# port-expander.net
KiCad netlist of a schematic drawn in Altium Designer
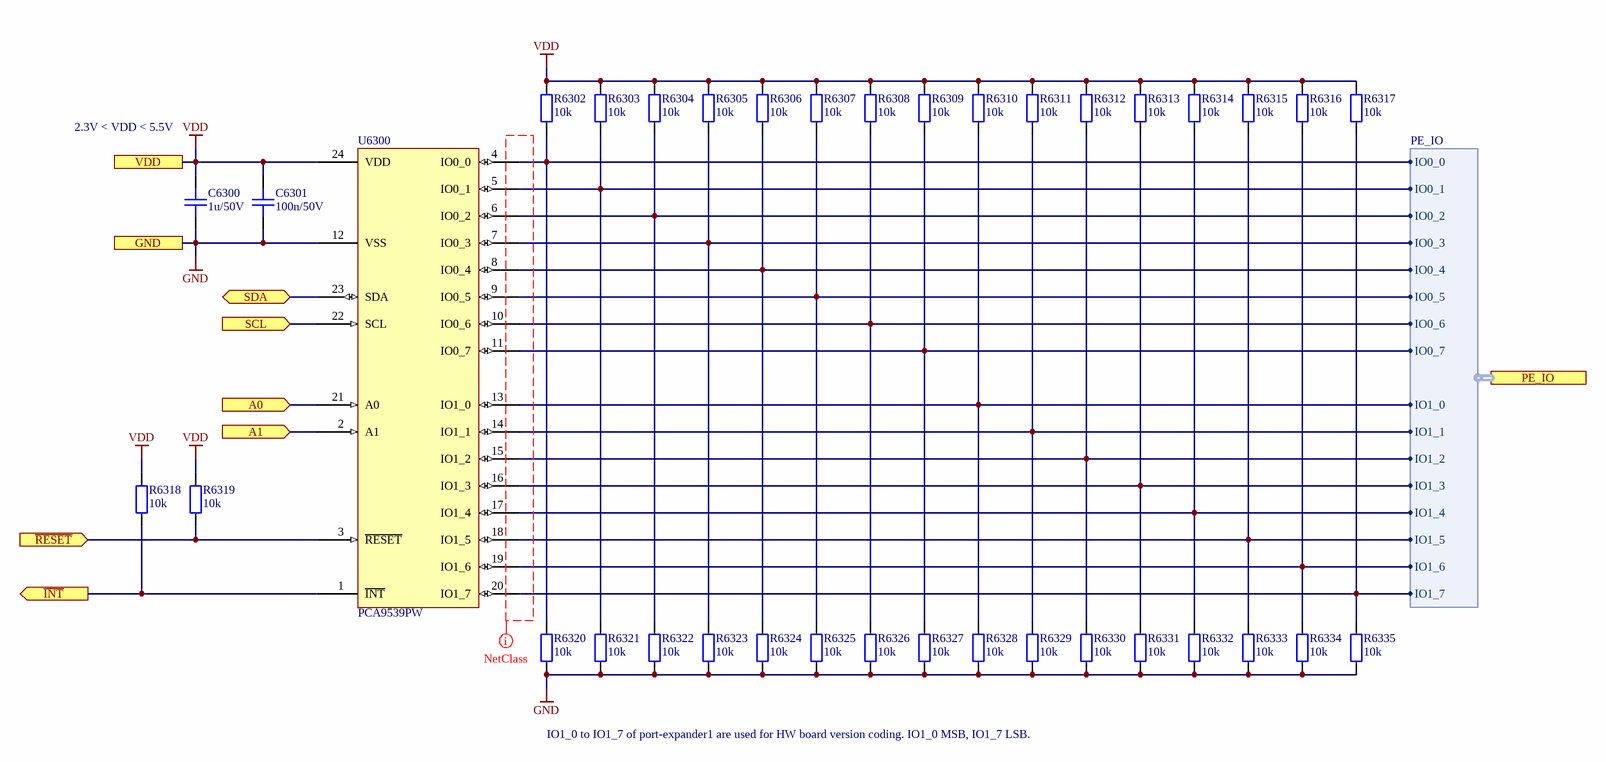
[diagram p0: port-expander.SchDoc]

(export (version "E")
  (design (tool "Eeschema 10.0.6"))
  (components
    (comp (ref "C6300")
      (value "1u/50V")
      (footprint "CAPC1608X08N")
      (description "MLCC")
      (fields (field (name "PART NUMBER") "gen_C_ceramic_1u_50V_X7R_0603") (field (name "TOLERANCE") "± 10%"))
      (libsource (lib "OE750") (part "C"))
    )
    (comp (ref "C6301")
      (value "100n/50V")
      (footprint "CAPC1005X06N")
      (description "MLCC")
      (fields (field (name "PART NUMBER") "gen_C_ceramic_100n_50V_X7R_0402"))
      (libsource (lib "OE750") (part "C"))
    )
    (comp (ref "R6302")
      (value "10k")
      (footprint "RESC1005X04N")
      (description "SMD Resistor 10k 0402")
      (fields (field (name "PART NUMBER") "gen_R_10k_0402") (field (name "TOLERANCE") "1%"))
      (libsource (lib "OE750") (part "R"))
    )
    (comp (ref "R6303")
      (value "10k")
      (footprint "RESC1005X04N")
      (description "SMD Resistor 10k 0402")
      (fields (field (name "PART NUMBER") "gen_R_10k_0402") (field (name "TOLERANCE") "1%"))
      (libsource (lib "OE750") (part "R"))
    )
    (comp (ref "R6304")
      (value "10k")
      (footprint "RESC1005X04N")
      (description "SMD Resistor 10k 0402")
      (fields (field (name "PART NUMBER") "gen_R_10k_0402") (field (name "TOLERANCE") "1%"))
      (libsource (lib "OE750") (part "R"))
    )
    (comp (ref "R6305")
      (value "10k")
      (footprint "RESC1005X04N")
      (description "SMD Resistor 10k 0402")
      (fields (field (name "PART NUMBER") "gen_R_10k_0402") (field (name "TOLERANCE") "1%"))
      (libsource (lib "OE750") (part "R"))
    )
    (comp (ref "R6306")
      (value "10k")
      (footprint "RESC1005X04N")
      (description "SMD Resistor 10k 0402")
      (fields (field (name "PART NUMBER") "gen_R_10k_0402") (field (name "TOLERANCE") "1%"))
      (libsource (lib "OE750") (part "R"))
    )
    (comp (ref "R6307")
      (value "10k")
      (footprint "RESC1005X04N")
      (description "SMD Resistor 10k 0402")
      (fields (field (name "PART NUMBER") "gen_R_10k_0402") (field (name "TOLERANCE") "1%"))
      (libsource (lib "OE750") (part "R"))
    )
    (comp (ref "R6308")
      (value "10k")
      (footprint "RESC1005X04N")
      (description "SMD Resistor 10k 0402")
      (fields (field (name "PART NUMBER") "gen_R_10k_0402") (field (name "TOLERANCE") "1%"))
      (libsource (lib "OE750") (part "R"))
    )
    (comp (ref "R6309")
      (value "10k")
      (footprint "RESC1005X04N")
      (description "SMD Resistor 10k 0402")
      (fields (field (name "PART NUMBER") "gen_R_10k_0402") (field (name "TOLERANCE") "1%"))
      (libsource (lib "OE750") (part "R"))
    )
    (comp (ref "R6310")
      (value "10k")
      (footprint "RESC1005X04N")
      (description "SMD Resistor 10k 0402")
      (fields (field (name "PART NUMBER") "gen_R_10k_0402") (field (name "TOLERANCE") "1%"))
      (libsource (lib "OE750") (part "R"))
    )
    (comp (ref "R6311")
      (value "10k")
      (footprint "RESC1005X04N")
      (description "SMD Resistor 10k 0402")
      (fields (field (name "PART NUMBER") "gen_R_10k_0402") (field (name "TOLERANCE") "1%"))
      (libsource (lib "OE750") (part "R"))
    )
    (comp (ref "R6312")
      (value "10k")
      (footprint "RESC1005X04N")
      (description "SMD Resistor 10k 0402")
      (fields (field (name "PART NUMBER") "gen_R_10k_0402") (field (name "TOLERANCE") "1%"))
      (libsource (lib "OE750") (part "R"))
    )
    (comp (ref "R6313")
      (value "10k")
      (footprint "RESC1005X04N")
      (description "SMD Resistor 10k 0402")
      (fields (field (name "PART NUMBER") "gen_R_10k_0402") (field (name "TOLERANCE") "1%"))
      (libsource (lib "OE750") (part "R"))
    )
    (comp (ref "R6314")
      (value "10k")
      (footprint "RESC1005X04N")
      (description "SMD Resistor 10k 0402")
      (fields (field (name "PART NUMBER") "gen_R_10k_0402") (field (name "TOLERANCE") "1%"))
      (libsource (lib "OE750") (part "R"))
    )
    (comp (ref "R6315")
      (value "10k")
      (footprint "RESC1005X04N")
      (description "SMD Resistor 10k 0402")
      (fields (field (name "PART NUMBER") "gen_R_10k_0402") (field (name "TOLERANCE") "1%"))
      (libsource (lib "OE750") (part "R"))
    )
    (comp (ref "R6316")
      (value "10k")
      (footprint "RESC1005X04N")
      (description "SMD Resistor 10k 0402")
      (fields (field (name "PART NUMBER") "gen_R_10k_0402") (field (name "TOLERANCE") "1%"))
      (libsource (lib "OE750") (part "R"))
    )
    (comp (ref "R6317")
      (value "10k")
      (footprint "RESC1005X04N")
      (description "SMD Resistor 10k 0402")
      (fields (field (name "PART NUMBER") "gen_R_10k_0402") (field (name "TOLERANCE") "1%"))
      (libsource (lib "OE750") (part "R"))
    )
    (comp (ref "R6318")
      (value "10k")
      (footprint "RESC1005X04N")
      (description "SMD Resistor 10k 0402")
      (fields (field (name "PART NUMBER") "gen_R_10k_0402") (field (name "TOLERANCE") "1%"))
      (libsource (lib "OE750") (part "R"))
    )
    (comp (ref "R6319")
      (value "10k")
      (footprint "RESC1005X04N")
      (description "SMD Resistor 10k 0402")
      (fields (field (name "PART NUMBER") "gen_R_10k_0402") (field (name "TOLERANCE") "1%"))
      (libsource (lib "OE750") (part "R"))
    )
    (comp (ref "R6320")
      (value "10k")
      (footprint "RESC1005X04N")
      (description "SMD Resistor 10k 0402")
      (fields (field (name "PART NUMBER") "gen_R_10k_0402") (field (name "TOLERANCE") "1%"))
      (libsource (lib "OE750") (part "R"))
    )
    (comp (ref "R6321")
      (value "10k")
      (footprint "RESC1005X04N")
      (description "SMD Resistor 10k 0402")
      (fields (field (name "PART NUMBER") "gen_R_10k_0402") (field (name "TOLERANCE") "1%"))
      (libsource (lib "OE750") (part "R"))
    )
    (comp (ref "R6322")
      (value "10k")
      (footprint "RESC1005X04N")
      (description "SMD Resistor 10k 0402")
      (fields (field (name "PART NUMBER") "gen_R_10k_0402") (field (name "TOLERANCE") "1%"))
      (libsource (lib "OE750") (part "R"))
    )
    (comp (ref "R6323")
      (value "10k")
      (footprint "RESC1005X04N")
      (description "SMD Resistor 10k 0402")
      (fields (field (name "PART NUMBER") "gen_R_10k_0402") (field (name "TOLERANCE") "1%"))
      (libsource (lib "OE750") (part "R"))
    )
    (comp (ref "R6324")
      (value "10k")
      (footprint "RESC1005X04N")
      (description "SMD Resistor 10k 0402")
      (fields (field (name "PART NUMBER") "gen_R_10k_0402") (field (name "TOLERANCE") "1%"))
      (libsource (lib "OE750") (part "R"))
    )
    (comp (ref "R6325")
      (value "10k")
      (footprint "RESC1005X04N")
      (description "SMD Resistor 10k 0402")
      (fields (field (name "PART NUMBER") "gen_R_10k_0402") (field (name "TOLERANCE") "1%"))
      (libsource (lib "OE750") (part "R"))
    )
    (comp (ref "R6326")
      (value "10k")
      (footprint "RESC1005X04N")
      (description "SMD Resistor 10k 0402")
      (fields (field (name "PART NUMBER") "gen_R_10k_0402") (field (name "TOLERANCE") "1%"))
      (libsource (lib "OE750") (part "R"))
    )
    (comp (ref "R6327")
      (value "10k")
      (footprint "RESC1005X04N")
      (description "SMD Resistor 10k 0402")
      (fields (field (name "PART NUMBER") "gen_R_10k_0402") (field (name "TOLERANCE") "1%"))
      (libsource (lib "OE750") (part "R"))
    )
    (comp (ref "R6328")
      (value "10k")
      (footprint "RESC1005X04N")
      (description "SMD Resistor 10k 0402")
      (fields (field (name "PART NUMBER") "gen_R_10k_0402") (field (name "TOLERANCE") "1%"))
      (libsource (lib "OE750") (part "R"))
    )
    (comp (ref "R6329")
      (value "10k")
      (footprint "RESC1005X04N")
      (description "SMD Resistor 10k 0402")
      (fields (field (name "PART NUMBER") "gen_R_10k_0402") (field (name "TOLERANCE") "1%"))
      (libsource (lib "OE750") (part "R"))
    )
    (comp (ref "R6330")
      (value "10k")
      (footprint "RESC1005X04N")
      (description "SMD Resistor 10k 0402")
      (fields (field (name "PART NUMBER") "gen_R_10k_0402") (field (name "TOLERANCE") "1%"))
      (libsource (lib "OE750") (part "R"))
    )
    (comp (ref "R6331")
      (value "10k")
      (footprint "RESC1005X04N")
      (description "SMD Resistor 10k 0402")
      (fields (field (name "PART NUMBER") "gen_R_10k_0402") (field (name "TOLERANCE") "1%"))
      (libsource (lib "OE750") (part "R"))
    )
    (comp (ref "R6332")
      (value "10k")
      (footprint "RESC1005X04N")
      (description "SMD Resistor 10k 0402")
      (fields (field (name "PART NUMBER") "gen_R_10k_0402") (field (name "TOLERANCE") "1%"))
      (libsource (lib "OE750") (part "R"))
    )
    (comp (ref "R6333")
      (value "10k")
      (footprint "RESC1005X04N")
      (description "SMD Resistor 10k 0402")
      (fields (field (name "PART NUMBER") "gen_R_10k_0402") (field (name "TOLERANCE") "1%"))
      (libsource (lib "OE750") (part "R"))
    )
    (comp (ref "R6334")
      (value "10k")
      (footprint "RESC1005X04N")
      (description "SMD Resistor 10k 0402")
      (fields (field (name "PART NUMBER") "gen_R_10k_0402") (field (name "TOLERANCE") "1%"))
      (libsource (lib "OE750") (part "R"))
    )
    (comp (ref "R6335")
      (value "10k")
      (footprint "RESC1005X04N")
      (description "SMD Resistor 10k 0402")
      (fields (field (name "PART NUMBER") "gen_R_10k_0402") (field (name "TOLERANCE") "1%"))
      (libsource (lib "OE750") (part "R"))
    )
    (comp (ref "U6300")
      (value "PCA9539PW")
      (footprint "PCA9539PW")
      (description "16-bit I2C-bus and SMBus low power I/O port with interrupt and reset")
      (fields (field (name "MANUFACTURER") "NXP"))
      (libsource (lib "OE750") (part "PCA9539PW"))
    )
  )
  (nets
    (net (code "2") (name "/A0") (class "Default")
      (node (ref "U6300") (pin "21") (pinfunction "A0_21") (pintype "input"))
    )
    (net (code "3") (name "/A1") (class "Default")
      (node (ref "U6300") (pin "2") (pinfunction "A1_2") (pintype "input"))
    )
    (net (code "4") (name "/INT") (class "Default")
      (node (ref "R6318") (pin "1") (pinfunction "1_1") (pintype "passive"))
      (node (ref "U6300") (pin "1") (pinfunction "INT_1") (pintype "open_collector"))
    )
    (net (code "5") (name "/RESET") (class "Default")
      (node (ref "R6319") (pin "1") (pinfunction "1_1") (pintype "passive"))
      (node (ref "U6300") (pin "3") (pinfunction "RESET_3") (pintype "input"))
    )
    (net (code "6") (name "/SCL") (class "Default")
      (node (ref "U6300") (pin "22") (pinfunction "SCL_22") (pintype "input"))
    )
    (net (code "7") (name "/SDA") (class "Default")
      (node (ref "U6300") (pin "23") (pinfunction "SDA_23") (pintype "bidirectional"))
    )
    (net (code "9") (name "GND") (class "Default")
      (node (ref "C6300") (pin "1") (pinfunction "1_1") (pintype "passive"))
      (node (ref "C6301") (pin "1") (pinfunction "1_1") (pintype "passive"))
      (node (ref "R6320") (pin "1") (pinfunction "1_1") (pintype "passive"))
      (node (ref "R6321") (pin "1") (pinfunction "1_1") (pintype "passive"))
      (node (ref "R6322") (pin "1") (pinfunction "1_1") (pintype "passive"))
      (node (ref "R6323") (pin "1") (pinfunction "1_1") (pintype "passive"))
      (node (ref "R6324") (pin "1") (pinfunction "1_1") (pintype "passive"))
      (node (ref "R6325") (pin "1") (pinfunction "1_1") (pintype "passive"))
      (node (ref "R6326") (pin "1") (pinfunction "1_1") (pintype "passive"))
      (node (ref "R6327") (pin "1") (pinfunction "1_1") (pintype "passive"))
      (node (ref "R6328") (pin "1") (pinfunction "1_1") (pintype "passive"))
      (node (ref "R6329") (pin "1") (pinfunction "1_1") (pintype "passive"))
      (node (ref "R6330") (pin "1") (pinfunction "1_1") (pintype "passive"))
      (node (ref "R6331") (pin "1") (pinfunction "1_1") (pintype "passive"))
      (node (ref "R6332") (pin "1") (pinfunction "1_1") (pintype "passive"))
      (node (ref "R6333") (pin "1") (pinfunction "1_1") (pintype "passive"))
      (node (ref "R6334") (pin "1") (pinfunction "1_1") (pintype "passive"))
      (node (ref "R6335") (pin "1") (pinfunction "1_1") (pintype "passive"))
      (node (ref "U6300") (pin "12") (pinfunction "VSS_12") (pintype "power_in"))
    )
    (net (code "10") (name "Net-(U6300-IO0_0)") (class "Default")
      (node (ref "R6302") (pin "1") (pinfunction "1_1") (pintype "passive"))
      (node (ref "R6320") (pin "2") (pinfunction "2_2") (pintype "passive"))
      (node (ref "U6300") (pin "4") (pinfunction "IO0_0_4") (pintype "bidirectional"))
    )
    (net (code "11") (name "Net-(U6300-IO0_1)") (class "Default")
      (node (ref "R6303") (pin "1") (pinfunction "1_1") (pintype "passive"))
      (node (ref "R6321") (pin "2") (pinfunction "2_2") (pintype "passive"))
      (node (ref "U6300") (pin "5") (pinfunction "IO0_1_5") (pintype "bidirectional"))
    )
    (net (code "12") (name "Net-(U6300-IO0_2)") (class "Default")
      (node (ref "R6304") (pin "1") (pinfunction "1_1") (pintype "passive"))
      (node (ref "R6322") (pin "2") (pinfunction "2_2") (pintype "passive"))
      (node (ref "U6300") (pin "6") (pinfunction "IO0_2_6") (pintype "bidirectional"))
    )
    (net (code "13") (name "Net-(U6300-IO0_3)") (class "Default")
      (node (ref "R6305") (pin "1") (pinfunction "1_1") (pintype "passive"))
      (node (ref "R6323") (pin "2") (pinfunction "2_2") (pintype "passive"))
      (node (ref "U6300") (pin "7") (pinfunction "IO0_3_7") (pintype "bidirectional"))
    )
    (net (code "14") (name "Net-(U6300-IO0_4)") (class "Default")
      (node (ref "R6306") (pin "1") (pinfunction "1_1") (pintype "passive"))
      (node (ref "R6324") (pin "2") (pinfunction "2_2") (pintype "passive"))
      (node (ref "U6300") (pin "8") (pinfunction "IO0_4_8") (pintype "bidirectional"))
    )
    (net (code "15") (name "Net-(U6300-IO0_5)") (class "Default")
      (node (ref "R6307") (pin "1") (pinfunction "1_1") (pintype "passive"))
      (node (ref "R6325") (pin "2") (pinfunction "2_2") (pintype "passive"))
      (node (ref "U6300") (pin "9") (pinfunction "IO0_5_9") (pintype "bidirectional"))
    )
    (net (code "16") (name "Net-(U6300-IO0_6)") (class "Default")
      (node (ref "R6308") (pin "1") (pinfunction "1_1") (pintype "passive"))
      (node (ref "R6326") (pin "2") (pinfunction "2_2") (pintype "passive"))
      (node (ref "U6300") (pin "10") (pinfunction "IO0_6_10") (pintype "bidirectional"))
    )
    (net (code "17") (name "Net-(U6300-IO0_7)") (class "Default")
      (node (ref "R6309") (pin "1") (pinfunction "1_1") (pintype "passive"))
      (node (ref "R6327") (pin "2") (pinfunction "2_2") (pintype "passive"))
      (node (ref "U6300") (pin "11") (pinfunction "IO0_7_11") (pintype "bidirectional"))
    )
    (net (code "18") (name "Net-(U6300-IO1_0)") (class "Default")
      (node (ref "R6310") (pin "1") (pinfunction "1_1") (pintype "passive"))
      (node (ref "R6328") (pin "2") (pinfunction "2_2") (pintype "passive"))
      (node (ref "U6300") (pin "13") (pinfunction "IO1_0_13") (pintype "bidirectional"))
    )
    (net (code "19") (name "Net-(U6300-IO1_1)") (class "Default")
      (node (ref "R6311") (pin "1") (pinfunction "1_1") (pintype "passive"))
      (node (ref "R6329") (pin "2") (pinfunction "2_2") (pintype "passive"))
      (node (ref "U6300") (pin "14") (pinfunction "IO1_1_14") (pintype "bidirectional"))
    )
    (net (code "20") (name "Net-(U6300-IO1_2)") (class "Default")
      (node (ref "R6312") (pin "1") (pinfunction "1_1") (pintype "passive"))
      (node (ref "R6330") (pin "2") (pinfunction "2_2") (pintype "passive"))
      (node (ref "U6300") (pin "15") (pinfunction "IO1_2_15") (pintype "bidirectional"))
    )
    (net (code "21") (name "Net-(U6300-IO1_3)") (class "Default")
      (node (ref "R6313") (pin "1") (pinfunction "1_1") (pintype "passive"))
      (node (ref "R6331") (pin "2") (pinfunction "2_2") (pintype "passive"))
      (node (ref "U6300") (pin "16") (pinfunction "IO1_3_16") (pintype "bidirectional"))
    )
    (net (code "22") (name "Net-(U6300-IO1_4)") (class "Default")
      (node (ref "R6314") (pin "1") (pinfunction "1_1") (pintype "passive"))
      (node (ref "R6332") (pin "2") (pinfunction "2_2") (pintype "passive"))
      (node (ref "U6300") (pin "17") (pinfunction "IO1_4_17") (pintype "bidirectional"))
    )
    (net (code "23") (name "Net-(U6300-IO1_5)") (class "Default")
      (node (ref "R6315") (pin "1") (pinfunction "1_1") (pintype "passive"))
      (node (ref "R6333") (pin "2") (pinfunction "2_2") (pintype "passive"))
      (node (ref "U6300") (pin "18") (pinfunction "IO1_5_18") (pintype "bidirectional"))
    )
    (net (code "24") (name "Net-(U6300-IO1_6)") (class "Default")
      (node (ref "R6316") (pin "1") (pinfunction "1_1") (pintype "passive"))
      (node (ref "R6334") (pin "2") (pinfunction "2_2") (pintype "passive"))
      (node (ref "U6300") (pin "19") (pinfunction "IO1_6_19") (pintype "bidirectional"))
    )
    (net (code "25") (name "Net-(U6300-IO1_7)") (class "Default")
      (node (ref "R6317") (pin "1") (pinfunction "1_1") (pintype "passive"))
      (node (ref "R6335") (pin "2") (pinfunction "2_2") (pintype "passive"))
      (node (ref "U6300") (pin "20") (pinfunction "IO1_7_20") (pintype "bidirectional"))
    )
    (net (code "26") (name "VDD") (class "Default")
      (node (ref "C6300") (pin "2") (pinfunction "2_2") (pintype "passive"))
      (node (ref "C6301") (pin "2") (pinfunction "2_2") (pintype "passive"))
      (node (ref "R6302") (pin "2") (pinfunction "2_2") (pintype "passive"))
      (node (ref "R6303") (pin "2") (pinfunction "2_2") (pintype "passive"))
      (node (ref "R6304") (pin "2") (pinfunction "2_2") (pintype "passive"))
      (node (ref "R6305") (pin "2") (pinfunction "2_2") (pintype "passive"))
      (node (ref "R6306") (pin "2") (pinfunction "2_2") (pintype "passive"))
      (node (ref "R6307") (pin "2") (pinfunction "2_2") (pintype "passive"))
      (node (ref "R6308") (pin "2") (pinfunction "2_2") (pintype "passive"))
      (node (ref "R6309") (pin "2") (pinfunction "2_2") (pintype "passive"))
      (node (ref "R6310") (pin "2") (pinfunction "2_2") (pintype "passive"))
      (node (ref "R6311") (pin "2") (pinfunction "2_2") (pintype "passive"))
      (node (ref "R6312") (pin "2") (pinfunction "2_2") (pintype "passive"))
      (node (ref "R6313") (pin "2") (pinfunction "2_2") (pintype "passive"))
      (node (ref "R6314") (pin "2") (pinfunction "2_2") (pintype "passive"))
      (node (ref "R6315") (pin "2") (pinfunction "2_2") (pintype "passive"))
      (node (ref "R6316") (pin "2") (pinfunction "2_2") (pintype "passive"))
      (node (ref "R6317") (pin "2") (pinfunction "2_2") (pintype "passive"))
      (node (ref "R6318") (pin "2") (pinfunction "2_2") (pintype "passive"))
      (node (ref "R6319") (pin "2") (pinfunction "2_2") (pintype "passive"))
      (node (ref "U6300") (pin "24") (pinfunction "VDD_24") (pintype "power_in"))
    )
  )
)
